# VEML6030-Breakout_v10.net
KiCad netlist of a schematic drawn in EAGLE
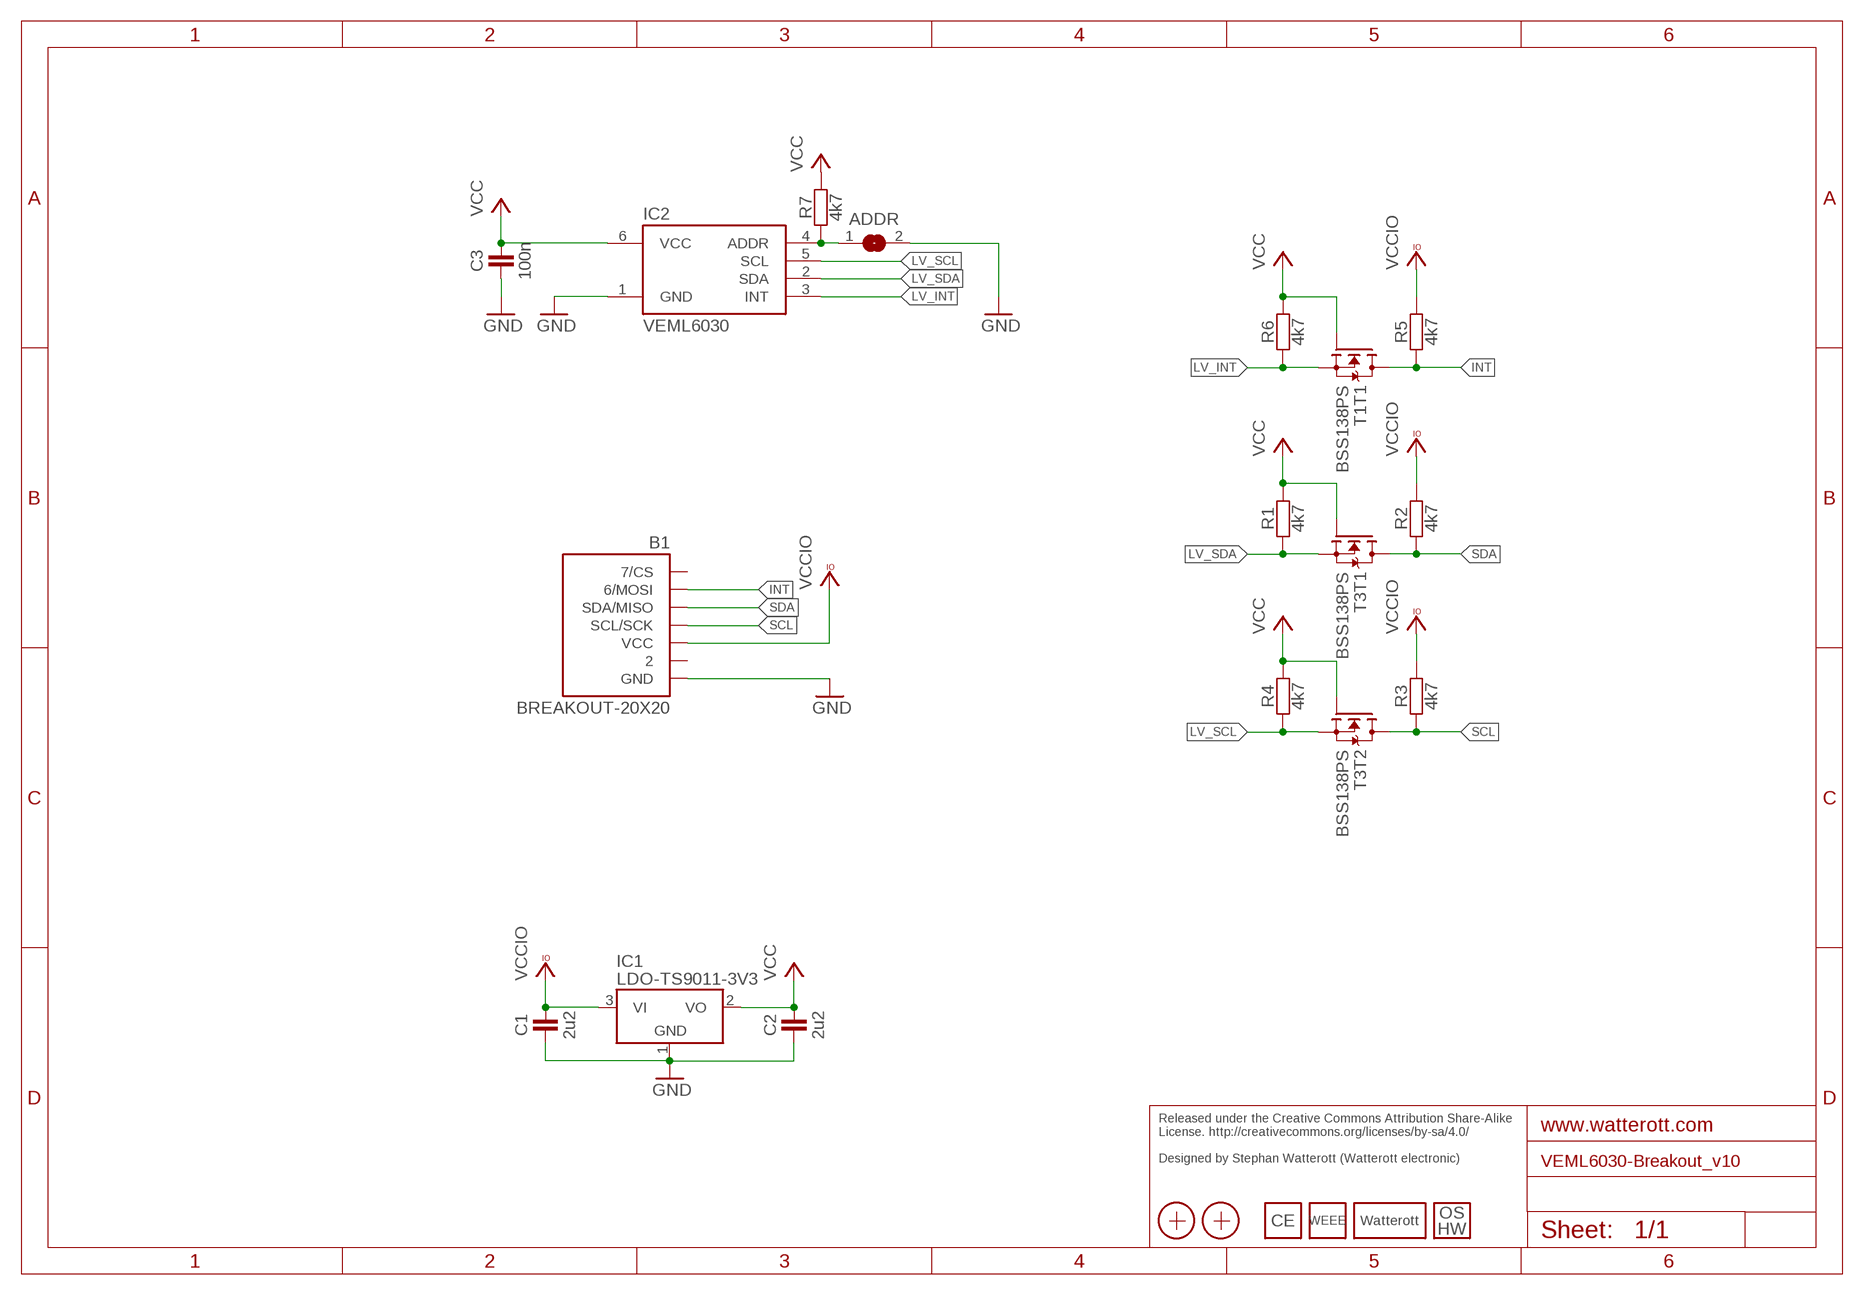
[diagram p0: schematic, sheet 1]

(export (version "E")
  (design (tool "Eeschema 10.0.6"))
  (components
    (comp (ref "ADDR")
      (value "JUMPER2-0603-NC")
      (footprint "eagle-import:JUMPER2-0603_NC")
      (libsource (lib "eagle-import") (part "JUMPER2-0603-NC"))
    )
    (comp (ref "B1")
      (value "BREAKOUT-20X20")
      (footprint "eagle-import:BREAKOUT-20X20")
      (libsource (lib "eagle-import") (part "BREAKOUT-20X20"))
    )
    (comp (ref "C1")
      (value "2u2")
      (footprint "eagle-import:C0402")
      (libsource (lib "eagle-import") (part "CAPACITOR-0402"))
    )
    (comp (ref "C2")
      (value "2u2")
      (footprint "eagle-import:C0402")
      (libsource (lib "eagle-import") (part "CAPACITOR-0402"))
    )
    (comp (ref "C3")
      (value "100n")
      (footprint "eagle-import:C0402")
      (libsource (lib "eagle-import") (part "CAPACITOR-0402"))
    )
    (comp (ref "IC1")
      (value "LDO-TS9011-3V3")
      (footprint "eagle-import:SOT23")
      (libsource (lib "eagle-import") (part "LDO-TS9011-3V3"))
    )
    (comp (ref "IC2")
      (value "VEML6030")
      (footprint "eagle-import:VEML6030")
      (libsource (lib "eagle-import") (part "VEML6030"))
    )
    (comp (ref "LOGO3")
      (value "LOGO_WEEE-4")
      (footprint "eagle-import:WEEE_4MM")
      (libsource (lib "eagle-import") (part "LOGO_WEEE-4"))
    )
    (comp (ref "LOGO4")
      (value "LOGO_CE-4")
      (footprint "eagle-import:CE_4MM")
      (libsource (lib "eagle-import") (part "LOGO_CE-4"))
    )
    (comp (ref "LOGO5")
      (value "LOGO_SPARK-4")
      (footprint "eagle-import:SPARK_4MM")
      (libsource (lib "eagle-import") (part "LOGO_SPARK-4"))
    )
    (comp (ref "LOGO6")
      (value "LOGO_OSHW-2")
      (footprint "eagle-import:OSHW_2MM")
      (libsource (lib "eagle-import") (part "LOGO_OSHW-2"))
    )
    (comp (ref "R1")
      (value "4k7")
      (footprint "eagle-import:C0402")
      (libsource (lib "eagle-import") (part "RESISTOR-0402"))
    )
    (comp (ref "R2")
      (value "4k7")
      (footprint "eagle-import:C0402")
      (libsource (lib "eagle-import") (part "RESISTOR-0402"))
    )
    (comp (ref "R3")
      (value "4k7")
      (footprint "eagle-import:C0402")
      (libsource (lib "eagle-import") (part "RESISTOR-0402"))
    )
    (comp (ref "R4")
      (value "4k7")
      (footprint "eagle-import:C0402")
      (libsource (lib "eagle-import") (part "RESISTOR-0402"))
    )
    (comp (ref "R5")
      (value "4k7")
      (footprint "eagle-import:C0402")
      (libsource (lib "eagle-import") (part "RESISTOR-0402"))
    )
    (comp (ref "R6")
      (value "4k7")
      (footprint "eagle-import:C0402")
      (libsource (lib "eagle-import") (part "RESISTOR-0402"))
    )
    (comp (ref "R7")
      (value "4k7")
      (footprint "eagle-import:C0402")
      (libsource (lib "eagle-import") (part "RESISTOR-0402"))
    )
    (comp (ref "T1")
      (value "BSS138PS")
      (footprint "eagle-import:SOT363")
      (libsource (lib "eagle-import") (part "BSS138PS"))
    )
    (comp (ref "T3")
      (value "BSS138PS")
      (footprint "eagle-import:SOT363")
      (libsource (lib "eagle-import") (part "BSS138PS"))
    )
    (comp (ref "X1")
      (value "PASSER-07")
      (footprint "eagle-import:PASSER_07MM")
      (libsource (lib "eagle-import") (part "PASSER-07"))
    )
    (comp (ref "X2")
      (value "PASSER-07")
      (footprint "eagle-import:PASSER_07MM")
      (libsource (lib "eagle-import") (part "PASSER-07"))
    )
  )
  (nets
    (net (code "1") (name "GND") (class "Default")
      (node (ref "ADDR") (pin "2") (pinfunction "2_2") (pintype "passive"))
      (node (ref "B1") (pin "GND") (pinfunction "GND_GND") (pintype "power_in"))
      (node (ref "C1") (pin "1") (pinfunction "1_1") (pintype "passive"))
      (node (ref "C2") (pin "1") (pinfunction "1_1") (pintype "passive"))
      (node (ref "C3") (pin "1") (pinfunction "1_1") (pintype "passive"))
      (node (ref "IC1") (pin "1") (pinfunction "GND_1") (pintype "passive"))
      (node (ref "IC2") (pin "1") (pinfunction "GND_1") (pintype "power_in"))
    )
    (net (code "2") (name "INT") (class "Default")
      (node (ref "B1") (pin "MOSI") (pinfunction "6/MOSI_MOSI") (pintype "bidirectional"))
      (node (ref "R5") (pin "1") (pinfunction "1_1") (pintype "passive"))
      (node (ref "T1") (pin "6") (pinfunction "D_6") (pintype "passive"))
    )
    (net (code "3") (name "LV_INT") (class "Default")
      (node (ref "IC2") (pin "3") (pinfunction "INT_3") (pintype "bidirectional"))
      (node (ref "R6") (pin "1") (pinfunction "1_1") (pintype "passive"))
      (node (ref "T1") (pin "1") (pinfunction "S_1") (pintype "passive"))
    )
    (net (code "4") (name "LV_SCL") (class "Default")
      (node (ref "IC2") (pin "5") (pinfunction "SCL_5") (pintype "bidirectional"))
      (node (ref "R4") (pin "1") (pinfunction "1_1") (pintype "passive"))
      (node (ref "T3") (pin "4") (pinfunction "S_4") (pintype "passive"))
    )
    (net (code "5") (name "LV_SDA") (class "Default")
      (node (ref "IC2") (pin "2") (pinfunction "SDA_2") (pintype "bidirectional"))
      (node (ref "R1") (pin "1") (pinfunction "1_1") (pintype "passive"))
      (node (ref "T3") (pin "1") (pinfunction "S_1") (pintype "passive"))
    )
    (net (code "6") (name "Net-(IC2-ADDR)") (class "Default")
      (node (ref "ADDR") (pin "1") (pinfunction "1_1") (pintype "passive"))
      (node (ref "IC2") (pin "4") (pinfunction "ADDR_4") (pintype "bidirectional"))
      (node (ref "R7") (pin "1") (pinfunction "1_1") (pintype "passive"))
    )
    (net (code "7") (name "SCL") (class "Default")
      (node (ref "B1") (pin "SCL/SCK") (pinfunction "SCL/SCK_SCL/SCK") (pintype "bidirectional"))
      (node (ref "R3") (pin "1") (pinfunction "1_1") (pintype "passive"))
      (node (ref "T3") (pin "3") (pinfunction "D_3") (pintype "passive"))
    )
    (net (code "8") (name "SDA") (class "Default")
      (node (ref "B1") (pin "SDA/MISO") (pinfunction "SDA/MISO_SDA/MISO") (pintype "bidirectional"))
      (node (ref "R2") (pin "1") (pinfunction "1_1") (pintype "passive"))
      (node (ref "T3") (pin "6") (pinfunction "D_6") (pintype "passive"))
    )
    (net (code "9") (name "VCC") (class "Default")
      (node (ref "C2") (pin "2") (pinfunction "2_2") (pintype "passive"))
      (node (ref "C3") (pin "2") (pinfunction "2_2") (pintype "passive"))
      (node (ref "IC1") (pin "2") (pinfunction "VO_2") (pintype "passive"))
      (node (ref "IC2") (pin "6") (pinfunction "VCC_6") (pintype "power_in"))
      (node (ref "R1") (pin "2") (pinfunction "2_2") (pintype "passive"))
      (node (ref "R4") (pin "2") (pinfunction "2_2") (pintype "passive"))
      (node (ref "R6") (pin "2") (pinfunction "2_2") (pintype "passive"))
      (node (ref "R7") (pin "2") (pinfunction "2_2") (pintype "passive"))
      (node (ref "T1") (pin "2") (pinfunction "G_2") (pintype "passive"))
      (node (ref "T3") (pin "2") (pinfunction "G_2") (pintype "passive"))
      (node (ref "T3") (pin "5") (pinfunction "G_5") (pintype "passive"))
    )
    (net (code "10") (name "VCCIO") (class "Default")
      (node (ref "B1") (pin "VCC") (pinfunction "VCC_VCC") (pintype "power_in"))
      (node (ref "C1") (pin "2") (pinfunction "2_2") (pintype "passive"))
      (node (ref "IC1") (pin "3") (pinfunction "VI_3") (pintype "input"))
      (node (ref "R2") (pin "2") (pinfunction "2_2") (pintype "passive"))
      (node (ref "R3") (pin "2") (pinfunction "2_2") (pintype "passive"))
      (node (ref "R5") (pin "2") (pinfunction "2_2") (pintype "passive"))
    )
    (net (code "11") (name "unconnected-(B1-7{slash}CS-PadCS)") (class "Default")
      (node (ref "B1") (pin "CS") (pinfunction "7/CS_CS") (pintype "bidirectional"))
    )
    (net (code "12") (name "unconnected-(B1-Pad2)") (class "Default")
      (node (ref "B1") (pin "2") (pinfunction "2_2") (pintype "bidirectional"))
    )
  )
)
